# MIXR_UI_-_Buttons.net
KiCad netlist of a schematic drawn in Altium Designer
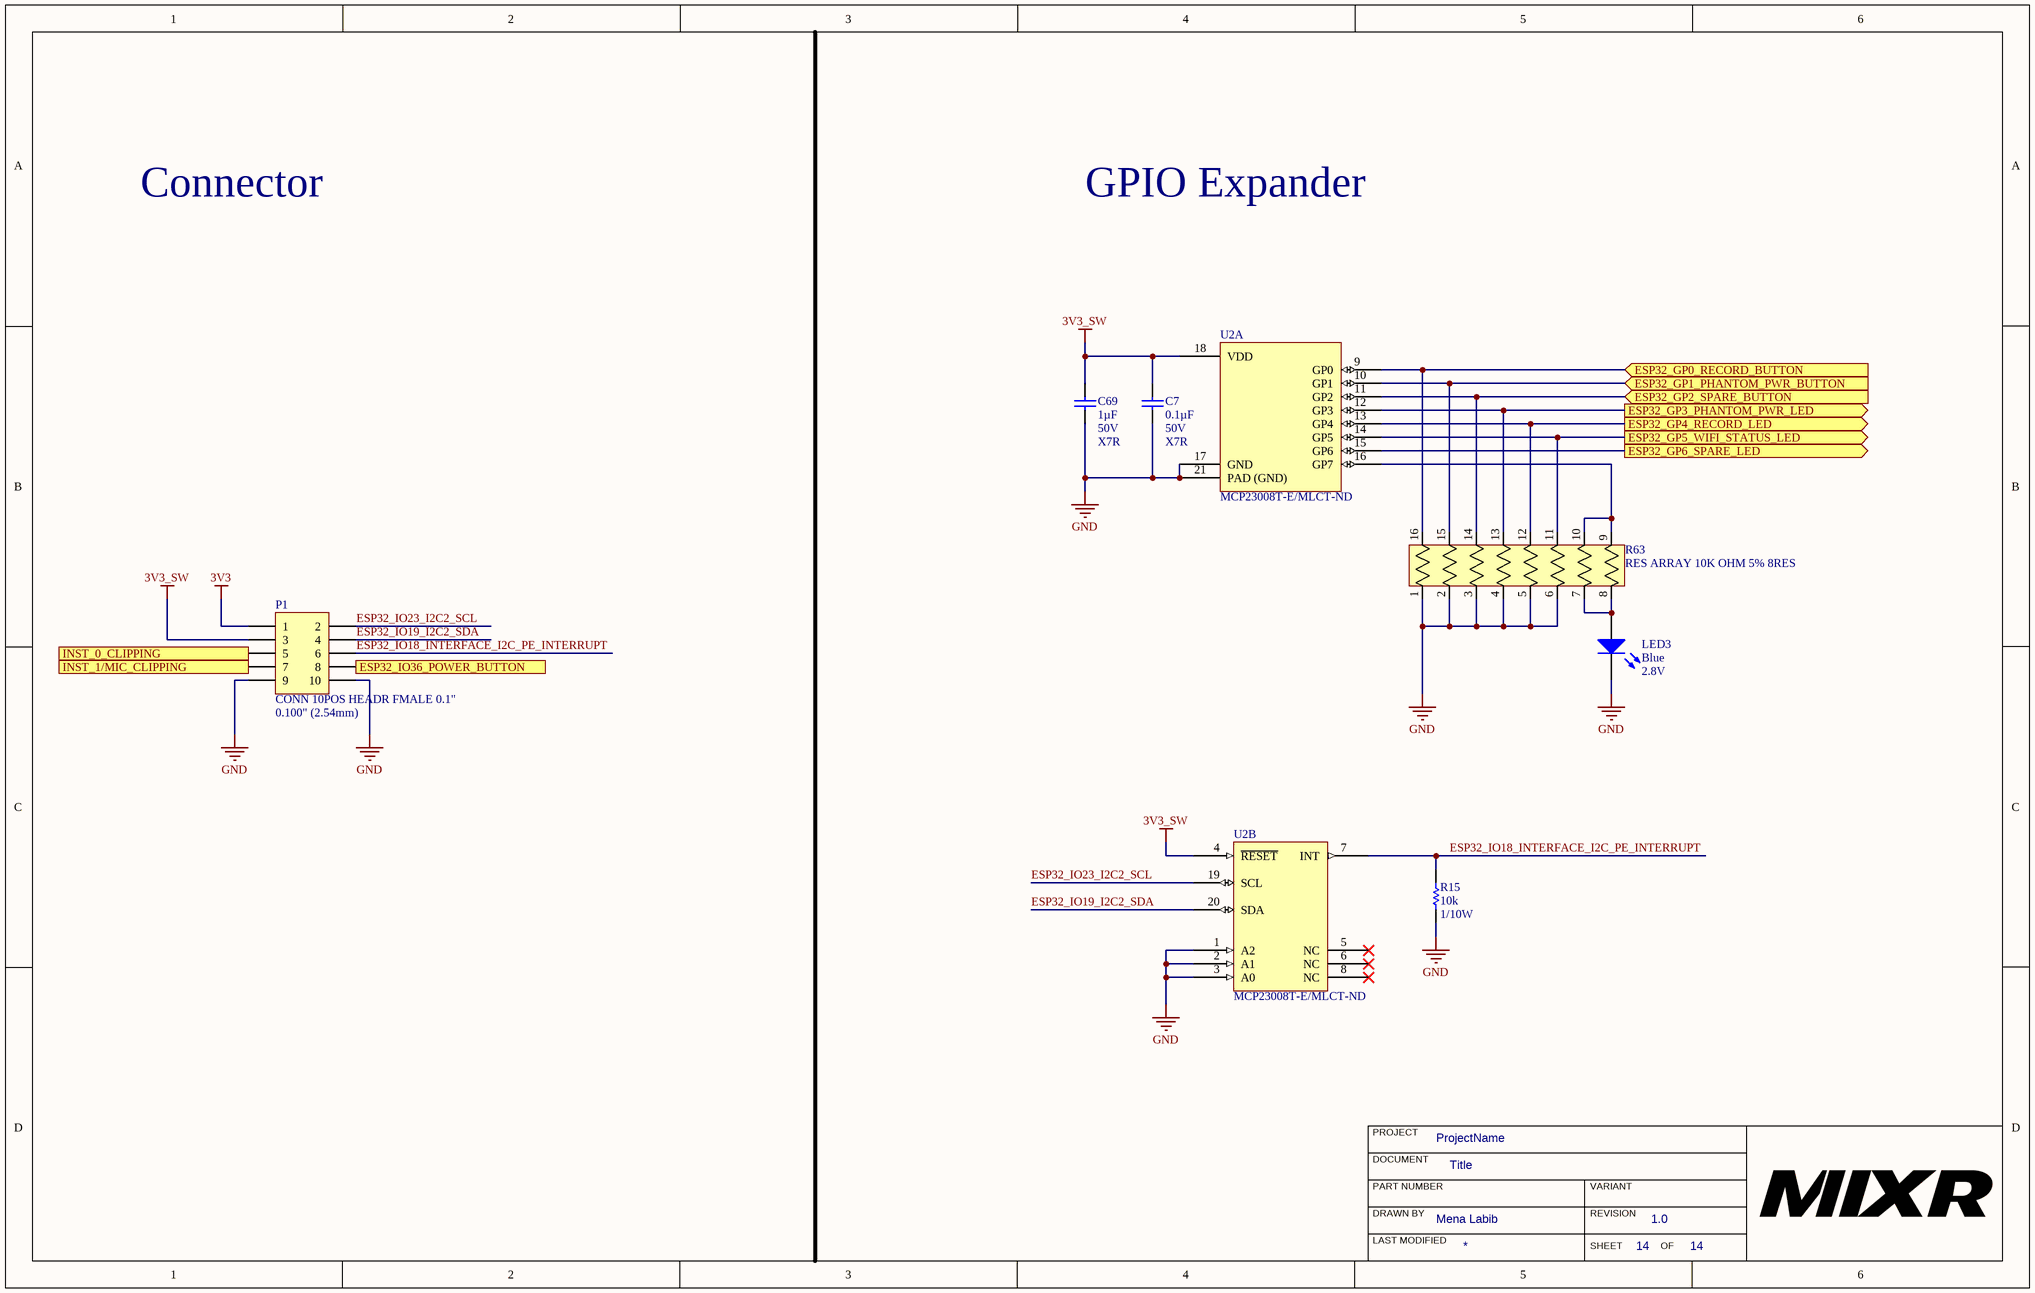
[diagram p0: MIXR UI - Buttons.SchDoc]

(export (version "E")
  (design (tool "Eeschema 10.0.6"))
  (components
    (comp (ref "C7")
      (value "CAP CER 0.1UF 50V 10% X7R 0603")
      (footprint "CAP, 0603")
      (description "0.10µF ±10% 50V Ceramic Capacitor X7R 0603 (1608 Metric)")
      (fields
        (field (name "TOLERANCE") "±10%")
        (field (name "CAPACITANCE") "0.1µF")
        (field (name "VOLTAGE") "50V")
        (field (name "TEMPERATURE COEFFICIENT") "X7R")
      )
      (libsource (lib "altium-import") (part "root_0_CAP CER 0.1UF 50V 10% X7R 0603_"))
    )
    (comp (ref "C69")
      (value "CAP CER 1UF 50V 10% X7R 0603")
      (footprint "CAP, 0603")
      (description "1µF ±10% 50V Ceramic Capacitor X7R 0603 (1608 Metric)")
      (fields
        (field (name "TOLERANCE") "±10%")
        (field (name "CAPACITANCE") "1µF")
        (field (name "VOLTAGE") "50V")
        (field (name "TEMPERATURE COEFFICIENT") "X7R")
      )
      (libsource (lib "Schematic Diagrams") (part "CAP CER 1UF 50V 10% X7R 0603"))
    )
    (comp (ref "LED3")
      (value "LED BLUE CLEAR 2.8V 0603")
      (footprint "LED_0603")
      (description "Blue 470nm LED Indication - Discrete 2.8V 0603 (1608 Metric)")
      (fields (field (name "COLOR") "Blue") (field (name "VOLTAGE - FORWARD (VF) (TYP)") "2.8V"))
      (libsource (lib "Schematic Diagrams") (part "LED BLUE CLEAR 2.8V 0603"))
    )
    (comp (ref "P1")
      (value "CONN 10POS HEADR FMALE 0.1\"")
      (footprint "CONN ,10 POS Header 0.100\"")
      (description "10 Position Header Connector 0.100\" (2.54mm) Through Hole, Right Angle Gold")
      (fields (field (name "PITCH - MATING") "0.100\" (2.54mm)"))
      (libsource (lib "altium-import") (part "root_0_CONN 10POS HEADR FMALE 0.1{dblquote}_"))
    )
    (comp (ref "R15")
      (value "RES 10K OHM 1% 1/10W 0603")
      (footprint "RES, 0603")
      (description "RES SMD 10K OHM 1% 1/10W 0603")
      (fields
        (field (name "TOLERANCE") "±1%")
        (field (name "RESISTANCE") "10k")
        (field (name "POWER") "1/10W")
      )
      (libsource (lib "altium-import") (part "root_0_RES 10K OHM 1% 1/10W 0603_"))
    )
    (comp (ref "R63")
      (value "RES ARRAY 10K OHM 5% 8RES")
      (footprint "RES ARRAY, 8 POS 1506")
      (description "RES ARRAY SMD 10K 5% 62.5mW 1506")
      (fields
        (field (name "MANUFACTURER_PART_NUMBER") "EXB-2HV103JV")
        (field (name "MANUFACTURER") "Panasonic Electronic Components")
        (field (name "COPYRIGHT") "Copyright (C) 2015 Accelerated Designs. All rights reserved")
      )
      (libsource (lib "Schematic Diagrams") (part "RES ARRAY 10K OHM 5% 8RES EXB-2HV103JV"))
    )
    (comp (ref "U2")
      (value "MCP23008")
      (footprint "QFN50P400X400X100_HS-21M")
      (description "I/O Expander 8 I²C 1.7MHz 20-QFN-EP (4x4)")
      (fields (field (name "SUPPLIER PART NUMBER 1") "MCP23008T-E/MLCT-ND"))
      (libsource (lib "Schematic Diagrams") (part "IC I/O EXPANDER I2C 8CH 20 QFN"))
    )
  )
  (nets
    (net (code "1") (name "/ESP32_GP0_RECORD_BUTTON") (class "Default")
      (node (ref "R63") (pin "16") (pinfunction "16_16") (pintype "passive"))
      (node (ref "U2") (pin "9") (pinfunction "GP0_9") (pintype "bidirectional"))
    )
    (net (code "2") (name "/ESP32_GP1_PHANTOM_PWR_BUTTON") (class "Default")
      (node (ref "R63") (pin "15") (pinfunction "15_15") (pintype "passive"))
      (node (ref "U2") (pin "10") (pinfunction "GP1_10") (pintype "bidirectional"))
    )
    (net (code "3") (name "/ESP32_GP2_SPARE_BUTTON") (class "Default")
      (node (ref "R63") (pin "14") (pinfunction "14_14") (pintype "passive"))
      (node (ref "U2") (pin "11") (pinfunction "GP2_11") (pintype "bidirectional"))
    )
    (net (code "4") (name "/ESP32_GP3_PHANTOM_PWR_LED") (class "Default")
      (node (ref "R63") (pin "13") (pinfunction "13_13") (pintype "passive"))
      (node (ref "U2") (pin "12") (pinfunction "GP3_12") (pintype "bidirectional"))
    )
    (net (code "5") (name "/ESP32_GP4_RECORD_LED") (class "Default")
      (node (ref "R63") (pin "12") (pinfunction "12_12") (pintype "passive"))
      (node (ref "U2") (pin "13") (pinfunction "GP4_13") (pintype "bidirectional"))
    )
    (net (code "6") (name "/ESP32_GP5_WIFI_STATUS_LED") (class "Default")
      (node (ref "R63") (pin "11") (pinfunction "11_11") (pintype "passive"))
      (node (ref "U2") (pin "14") (pinfunction "GP5_14") (pintype "bidirectional"))
    )
    (net (code "7") (name "/ESP32_GP6_SPARE_LED") (class "Default")
      (node (ref "U2") (pin "15") (pinfunction "GP6_15") (pintype "bidirectional"))
    )
    (net (code "8") (name "/ESP32_IO18_INTERFACE_I2C_PE_INTERRUPT") (class "Default")
      (node (ref "P1") (pin "6") (pinfunction "6_6") (pintype "passive"))
      (node (ref "R15") (pin "1") (pinfunction "1_1") (pintype "passive"))
      (node (ref "U2") (pin "7") (pinfunction "INT_7") (pintype "output"))
    )
    (net (code "9") (name "/ESP32_IO19_I2C2_SDA") (class "Default")
      (node (ref "P1") (pin "4") (pinfunction "4_4") (pintype "passive"))
      (node (ref "U2") (pin "20") (pinfunction "SDA_20") (pintype "bidirectional"))
    )
    (net (code "10") (name "/ESP32_IO23_I2C2_SCL") (class "Default")
      (node (ref "P1") (pin "2") (pinfunction "2_2") (pintype "passive"))
      (node (ref "U2") (pin "19") (pinfunction "SCL_19") (pintype "bidirectional"))
    )
    (net (code "11") (name "/ESP32_IO36_POWER_BUTTON") (class "Default")
      (node (ref "P1") (pin "8") (pinfunction "8_8") (pintype "passive"))
    )
    (net (code "12") (name "/INST_0_CLIPPING") (class "Default")
      (node (ref "P1") (pin "5") (pinfunction "5_5") (pintype "passive"))
    )
    (net (code "13") (name "/INST_1{slash}MIC_CLIPPING") (class "Default")
      (node (ref "P1") (pin "7") (pinfunction "7_7") (pintype "passive"))
    )
    (net (code "14") (name "3V3") (class "Default")
      (node (ref "P1") (pin "1") (pinfunction "1_1") (pintype "passive"))
    )
    (net (code "15") (name "3V3_SW") (class "Default")
      (node (ref "C69") (pin "1") (pinfunction "1_1") (pintype "passive"))
      (node (ref "C7") (pin "1") (pinfunction "1_1") (pintype "passive"))
      (node (ref "P1") (pin "3") (pinfunction "3_3") (pintype "passive"))
      (node (ref "U2") (pin "18") (pinfunction "VDD_18") (pintype "power_in"))
      (node (ref "U2") (pin "4") (pinfunction "~{RESET}_4") (pintype "input"))
    )
    (net (code "16") (name "GND") (class "Default")
      (node (ref "C69") (pin "2") (pinfunction "2_2") (pintype "passive"))
      (node (ref "C7") (pin "2") (pinfunction "2_2") (pintype "passive"))
      (node (ref "LED3") (pin "2") (pinfunction "K_2") (pintype "passive"))
      (node (ref "P1") (pin "10") (pinfunction "10_10") (pintype "passive"))
      (node (ref "P1") (pin "9") (pinfunction "9_9") (pintype "passive"))
      (node (ref "R15") (pin "2") (pinfunction "2_2") (pintype "passive"))
      (node (ref "R63") (pin "1") (pinfunction "1_1") (pintype "passive"))
      (node (ref "R63") (pin "2") (pinfunction "2_2") (pintype "passive"))
      (node (ref "R63") (pin "3") (pinfunction "3_3") (pintype "passive"))
      (node (ref "R63") (pin "4") (pinfunction "4_4") (pintype "passive"))
      (node (ref "R63") (pin "5") (pinfunction "5_5") (pintype "passive"))
      (node (ref "R63") (pin "6") (pinfunction "6_6") (pintype "passive"))
      (node (ref "U2") (pin "1") (pinfunction "A2_1") (pintype "input"))
      (node (ref "U2") (pin "17") (pinfunction "GND_17") (pintype "power_in"))
      (node (ref "U2") (pin "2") (pinfunction "A1_2") (pintype "input"))
      (node (ref "U2") (pin "21") (pinfunction "PAD_(GND)_21") (pintype "power_in"))
      (node (ref "U2") (pin "3") (pinfunction "A0_3") (pintype "input"))
    )
    (net (code "17") (name "Net-(LED3-A)") (class "Default")
      (node (ref "LED3") (pin "1") (pinfunction "A_1") (pintype "passive"))
      (node (ref "R63") (pin "7") (pinfunction "7_7") (pintype "passive"))
      (node (ref "R63") (pin "8") (pinfunction "8_8") (pintype "passive"))
    )
    (net (code "18") (name "Net-(U2A-GP7)") (class "Default")
      (node (ref "R63") (pin "10") (pinfunction "10_10") (pintype "passive"))
      (node (ref "R63") (pin "9") (pinfunction "9_9") (pintype "passive"))
      (node (ref "U2") (pin "16") (pinfunction "GP7_16") (pintype "bidirectional"))
    )
    (net (code "19") (name "unconnected-(U2B-NC-Pad5)") (class "Default")
      (node (ref "U2") (pin "5") (pinfunction "NC_5") (pintype "passive+no_connect"))
    )
    (net (code "20") (name "unconnected-(U2B-NC-Pad6)") (class "Default")
      (node (ref "U2") (pin "6") (pinfunction "NC_6") (pintype "passive+no_connect"))
    )
    (net (code "21") (name "unconnected-(U2B-NC-Pad8)") (class "Default")
      (node (ref "U2") (pin "8") (pinfunction "NC_8") (pintype "passive+no_connect"))
    )
  )
)
